# motoko_ice_dragon_x_dc.net
KiCad netlist of a schematic drawn in EAGLE
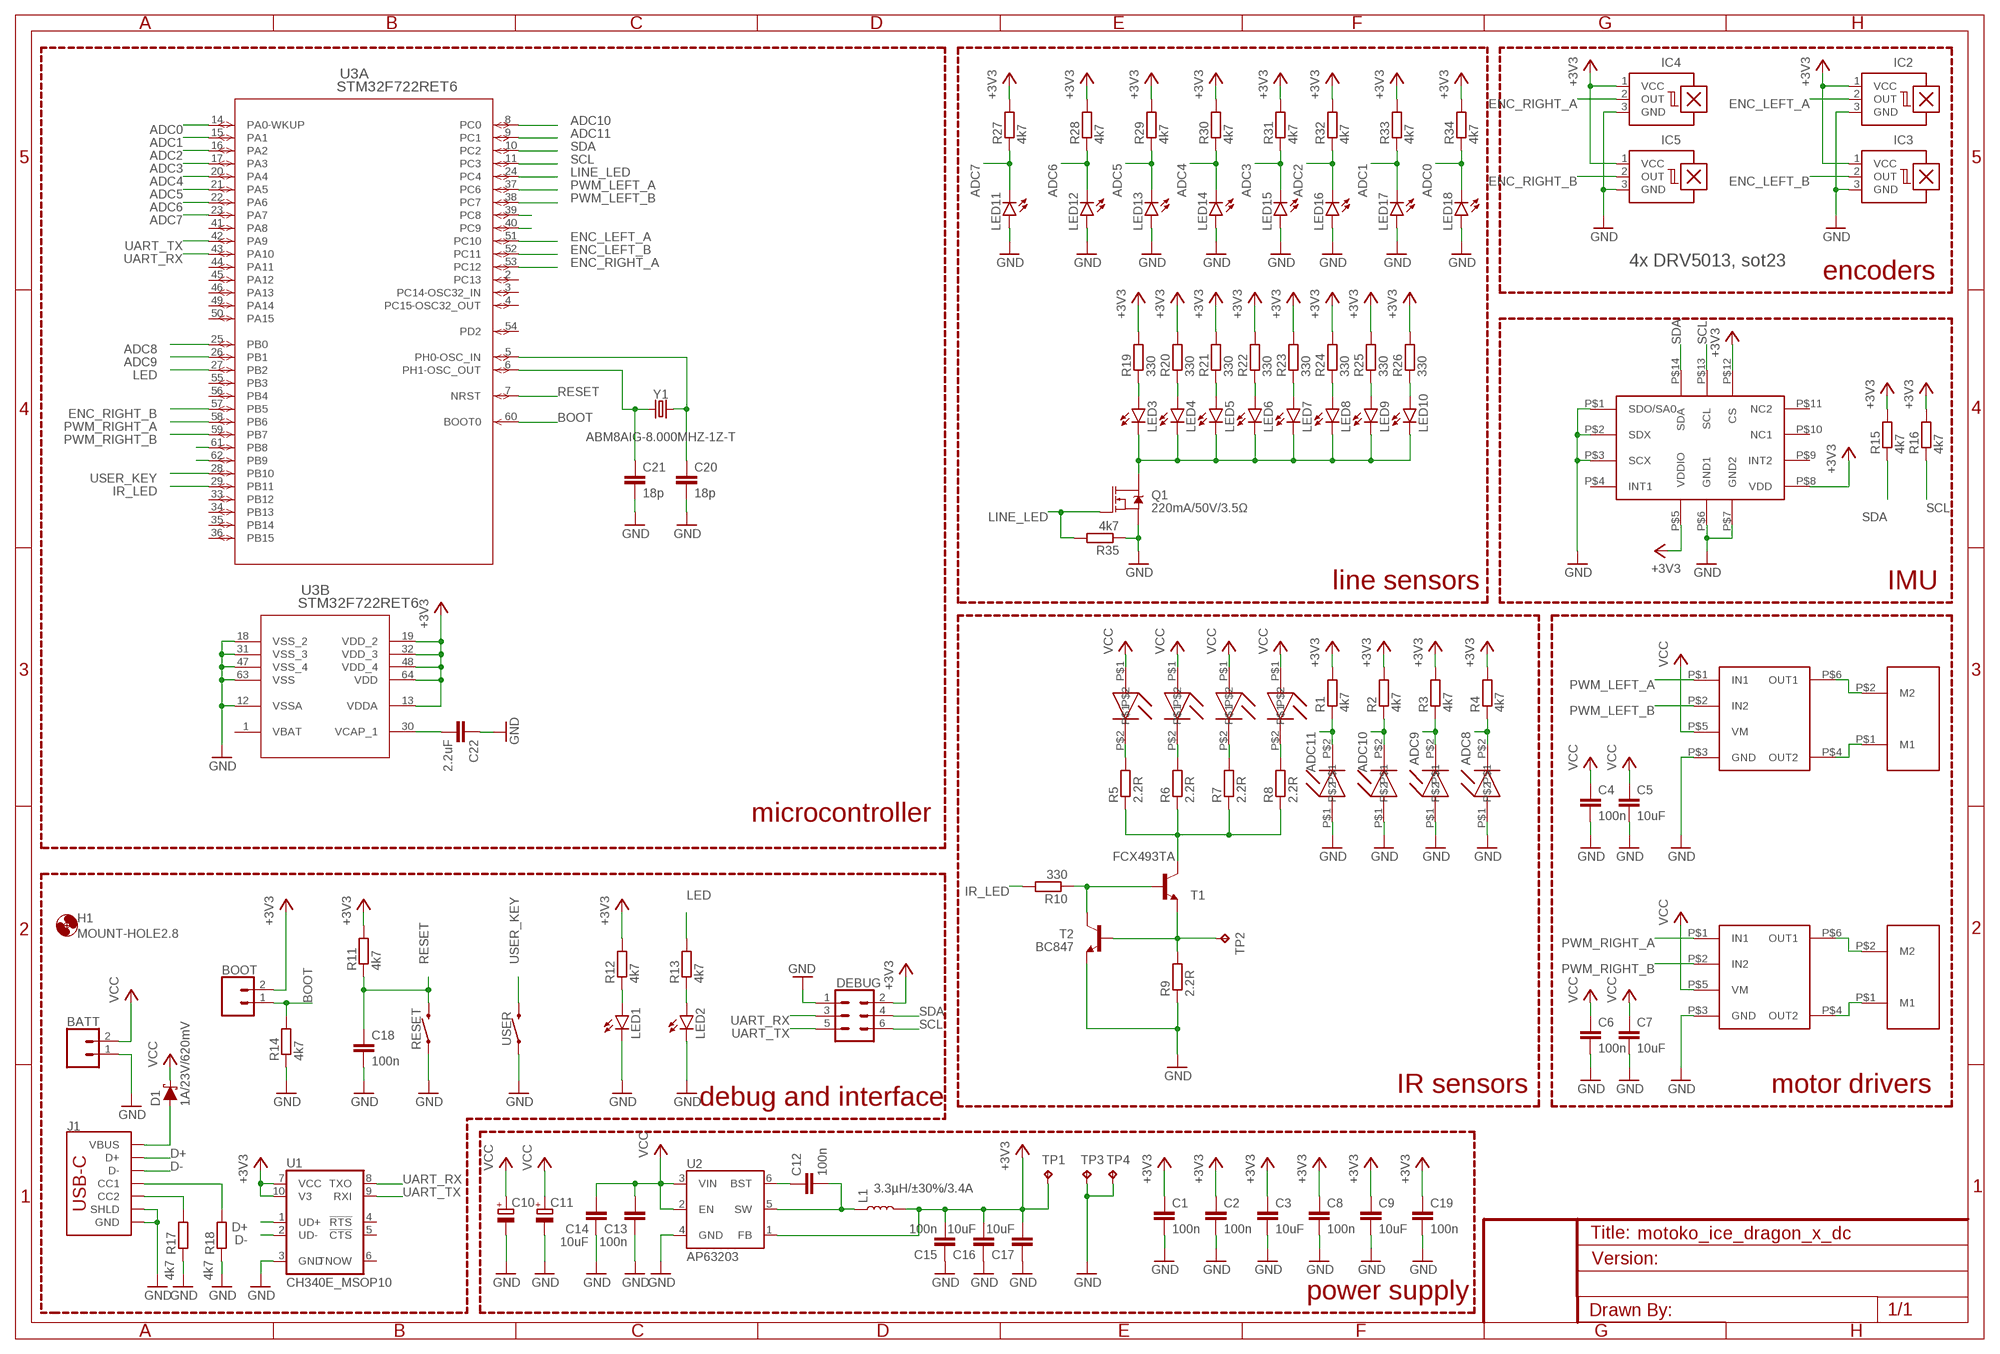
[diagram p0: schematic, sheet 1]

(export (version "E")
  (design (tool "Eeschema 10.0.6"))
  (components
    (comp (ref "BATT")
      (value "CONN_02LOCK_LONGPADS")
      (footprint "eagle-import:1X02_LOCK_LONGPADS")
      (libsource (lib "eagle-import") (part "CONN_02LOCK_LONGPADS"))
    )
    (comp (ref "BOOT")
      (value "CONN_02LOCK_LONGPADS")
      (footprint "eagle-import:1X02_LOCK_LONGPADS")
      (libsource (lib "eagle-import") (part "CONN_02LOCK_LONGPADS"))
    )
    (comp (ref "C1")
      (value "100n")
      (footprint "eagle-import:C0805")
      (libsource (lib "eagle-import") (part "C-EUC0805"))
    )
    (comp (ref "C2")
      (value "100n")
      (footprint "eagle-import:C0805")
      (libsource (lib "eagle-import") (part "C-EUC0805"))
    )
    (comp (ref "C3")
      (value "10uF")
      (footprint "eagle-import:C0805")
      (libsource (lib "eagle-import") (part "C-EUC0805"))
    )
    (comp (ref "C4")
      (value "100n")
      (footprint "eagle-import:C0805")
      (libsource (lib "eagle-import") (part "C-EUC0805"))
    )
    (comp (ref "C5")
      (value "10uF")
      (footprint "eagle-import:C0805")
      (libsource (lib "eagle-import") (part "C-EUC0805"))
    )
    (comp (ref "C6")
      (value "100n")
      (footprint "eagle-import:C0805")
      (libsource (lib "eagle-import") (part "C-EUC0805"))
    )
    (comp (ref "C7")
      (value "10uF")
      (footprint "eagle-import:C0805")
      (libsource (lib "eagle-import") (part "C-EUC0805"))
    )
    (comp (ref "C8")
      (value "100n")
      (footprint "eagle-import:C0805")
      (libsource (lib "eagle-import") (part "C-EUC0805"))
    )
    (comp (ref "C9")
      (value "10uF")
      (footprint "eagle-import:C0805")
      (libsource (lib "eagle-import") (part "C-EUC0805"))
    )
    (comp (ref "C10")
      (value "CPOL-EU140CLH-0810")
      (footprint "eagle-import:140CLH-0810")
      (libsource (lib "eagle-import") (part "CPOL-EU140CLH-0810"))
    )
    (comp (ref "C11")
      (value "CPOL-EU140CLH-0810")
      (footprint "eagle-import:140CLH-0810")
      (libsource (lib "eagle-import") (part "CPOL-EU140CLH-0810"))
    )
    (comp (ref "C12")
      (value "100n")
      (footprint "eagle-import:C0805")
      (libsource (lib "eagle-import") (part "C-EUC0805"))
    )
    (comp (ref "C13")
      (value "100n")
      (footprint "eagle-import:C0805")
      (libsource (lib "eagle-import") (part "C-EUC0805"))
    )
    (comp (ref "C14")
      (value "10uF")
      (footprint "eagle-import:C0805")
      (libsource (lib "eagle-import") (part "C-EUC0805"))
    )
    (comp (ref "C15")
      (value "100n")
      (footprint "eagle-import:C0805")
      (libsource (lib "eagle-import") (part "C-EUC0805"))
    )
    (comp (ref "C16")
      (value "10uF")
      (footprint "eagle-import:C0805")
      (libsource (lib "eagle-import") (part "C-EUC0805"))
    )
    (comp (ref "C17")
      (value "10uF")
      (footprint "eagle-import:C0805")
      (libsource (lib "eagle-import") (part "C-EUC0805"))
    )
    (comp (ref "C18")
      (value "100n")
      (footprint "eagle-import:C0805")
      (libsource (lib "eagle-import") (part "C-EUC0805"))
    )
    (comp (ref "C19")
      (value "100n")
      (footprint "eagle-import:C0805")
      (libsource (lib "eagle-import") (part "C-EUC0805"))
    )
    (comp (ref "C20")
      (value "18p")
      (footprint "eagle-import:C0805")
      (libsource (lib "eagle-import") (part "C-EUC0805"))
    )
    (comp (ref "C21")
      (value "18p")
      (footprint "eagle-import:C0805")
      (libsource (lib "eagle-import") (part "C-EUC0805"))
    )
    (comp (ref "C22")
      (value "2.2uF")
      (footprint "eagle-import:C0805")
      (libsource (lib "eagle-import") (part "C-EUC0805"))
    )
    (comp (ref "D1")
      (value "1A/23V/620mV")
      (footprint "eagle-import:SOD-323")
      (libsource (lib "eagle-import") (part "DIODE-SCHOTTKY-BAT20J"))
    )
    (comp (ref "DEBUG")
      (value "FEMALE 2x3")
      (footprint "eagle-import:2X3")
      (libsource (lib "eagle-import") (part "CONN_03X2FEMALE"))
    )
    (comp (ref "H1")
      (value "MOUNT-HOLE2.8")
      (footprint "eagle-import:2,8")
      (libsource (lib "eagle-import") (part "MOUNT-HOLE2.8"))
    )
    (comp (ref "IC2")
      (value "A1202LH")
      (footprint "eagle-import:SOT23-W")
      (libsource (lib "eagle-import") (part "A12?LH02"))
    )
    (comp (ref "IC3")
      (value "A1202LH")
      (footprint "eagle-import:SOT23-W")
      (libsource (lib "eagle-import") (part "A12?LH02"))
    )
    (comp (ref "IC4")
      (value "A1202LH")
      (footprint "eagle-import:SOT23-W")
      (libsource (lib "eagle-import") (part "A12?LH02"))
    )
    (comp (ref "IC5")
      (value "A1202LH")
      (footprint "eagle-import:SOT23-W")
      (libsource (lib "eagle-import") (part "A12?LH02"))
    )
    (comp (ref "J1")
      (value "640-USB4105-GF-A-120, man. GCT")
      (footprint "eagle-import:USB-C-16P-2LAYER-PADS")
      (libsource (lib "eagle-import") (part "USB_C_2-LAYER_PADS"))
    )
    (comp (ref "L1")
      (value "3.3µH/±30%/3.4A")
      (footprint "eagle-import:CR54")
      (libsource (lib "eagle-import") (part "INDUCTOR-CR54-3.3UH"))
    )
    (comp (ref "LED1")
      (value "LEDCHIPLED_1206")
      (footprint "eagle-import:CHIPLED_1206")
      (libsource (lib "eagle-import") (part "LEDCHIPLED_1206"))
    )
    (comp (ref "LED2")
      (value "LEDCHIPLED_1206")
      (footprint "eagle-import:CHIPLED_1206")
      (libsource (lib "eagle-import") (part "LEDCHIPLED_1206"))
    )
    (comp (ref "LED3")
      (value "LEDCHIPLED_1206")
      (footprint "eagle-import:CHIPLED_1206")
      (libsource (lib "eagle-import") (part "LEDCHIPLED_1206"))
    )
    (comp (ref "LED4")
      (value "LEDCHIPLED_1206")
      (footprint "eagle-import:CHIPLED_1206")
      (libsource (lib "eagle-import") (part "LEDCHIPLED_1206"))
    )
    (comp (ref "LED5")
      (value "LEDCHIPLED_1206")
      (footprint "eagle-import:CHIPLED_1206")
      (libsource (lib "eagle-import") (part "LEDCHIPLED_1206"))
    )
    (comp (ref "LED6")
      (value "LEDCHIPLED_1206")
      (footprint "eagle-import:CHIPLED_1206")
      (libsource (lib "eagle-import") (part "LEDCHIPLED_1206"))
    )
    (comp (ref "LED7")
      (value "LEDCHIPLED_1206")
      (footprint "eagle-import:CHIPLED_1206")
      (libsource (lib "eagle-import") (part "LEDCHIPLED_1206"))
    )
    (comp (ref "LED8")
      (value "LEDCHIPLED_1206")
      (footprint "eagle-import:CHIPLED_1206")
      (libsource (lib "eagle-import") (part "LEDCHIPLED_1206"))
    )
    (comp (ref "LED9")
      (value "LEDCHIPLED_1206")
      (footprint "eagle-import:CHIPLED_1206")
      (libsource (lib "eagle-import") (part "LEDCHIPLED_1206"))
    )
    (comp (ref "LED10")
      (value "LEDCHIPLED_1206")
      (footprint "eagle-import:CHIPLED_1206")
      (libsource (lib "eagle-import") (part "LEDCHIPLED_1206"))
    )
    (comp (ref "LED11")
      (value "LEDCHIPLED_1206")
      (footprint "eagle-import:CHIPLED_1206")
      (libsource (lib "eagle-import") (part "LEDCHIPLED_1206"))
    )
    (comp (ref "LED12")
      (value "LEDCHIPLED_1206")
      (footprint "eagle-import:CHIPLED_1206")
      (libsource (lib "eagle-import") (part "LEDCHIPLED_1206"))
    )
    (comp (ref "LED13")
      (value "LEDCHIPLED_1206")
      (footprint "eagle-import:CHIPLED_1206")
      (libsource (lib "eagle-import") (part "LEDCHIPLED_1206"))
    )
    (comp (ref "LED14")
      (value "LEDCHIPLED_1206")
      (footprint "eagle-import:CHIPLED_1206")
      (libsource (lib "eagle-import") (part "LEDCHIPLED_1206"))
    )
    (comp (ref "LED15")
      (value "LEDCHIPLED_1206")
      (footprint "eagle-import:CHIPLED_1206")
      (libsource (lib "eagle-import") (part "LEDCHIPLED_1206"))
    )
    (comp (ref "LED16")
      (value "LEDCHIPLED_1206")
      (footprint "eagle-import:CHIPLED_1206")
      (libsource (lib "eagle-import") (part "LEDCHIPLED_1206"))
    )
    (comp (ref "LED17")
      (value "LEDCHIPLED_1206")
      (footprint "eagle-import:CHIPLED_1206")
      (libsource (lib "eagle-import") (part "LEDCHIPLED_1206"))
    )
    (comp (ref "LED18")
      (value "LEDCHIPLED_1206")
      (footprint "eagle-import:CHIPLED_1206")
      (libsource (lib "eagle-import") (part "LEDCHIPLED_1206"))
    )
    (comp (ref "Q1")
      (value "220mA/50V/3.5Ω")
      (footprint "eagle-import:SOT23-3")
      (libsource (lib "eagle-import") (part "MOSFET-NCH-BSS138"))
    )
    (comp (ref "R1")
      (value "4k7")
      (footprint "eagle-import:M0805")
      (libsource (lib "eagle-import") (part "R-EU_M0805"))
    )
    (comp (ref "R2")
      (value "4k7")
      (footprint "eagle-import:M0805")
      (libsource (lib "eagle-import") (part "R-EU_M0805"))
    )
    (comp (ref "R3")
      (value "4k7")
      (footprint "eagle-import:M0805")
      (libsource (lib "eagle-import") (part "R-EU_M0805"))
    )
    (comp (ref "R4")
      (value "4k7")
      (footprint "eagle-import:M0805")
      (libsource (lib "eagle-import") (part "R-EU_M0805"))
    )
    (comp (ref "R5")
      (value "2.2R")
      (footprint "eagle-import:M0805")
      (libsource (lib "eagle-import") (part "R-EU_M0805"))
    )
    (comp (ref "R6")
      (value "2.2R")
      (footprint "eagle-import:M0805")
      (libsource (lib "eagle-import") (part "R-EU_M0805"))
    )
    (comp (ref "R7")
      (value "2.2R")
      (footprint "eagle-import:M0805")
      (libsource (lib "eagle-import") (part "R-EU_M0805"))
    )
    (comp (ref "R8")
      (value "2.2R")
      (footprint "eagle-import:M0805")
      (libsource (lib "eagle-import") (part "R-EU_M0805"))
    )
    (comp (ref "R9")
      (value "2.2R")
      (footprint "eagle-import:M0805")
      (libsource (lib "eagle-import") (part "R-EU_M0805"))
    )
    (comp (ref "R10")
      (value "330")
      (footprint "eagle-import:M0805")
      (libsource (lib "eagle-import") (part "R-EU_M0805"))
    )
    (comp (ref "R11")
      (value "4k7")
      (footprint "eagle-import:M0805")
      (libsource (lib "eagle-import") (part "R-EU_M0805"))
    )
    (comp (ref "R12")
      (value "4k7")
      (footprint "eagle-import:M0805")
      (libsource (lib "eagle-import") (part "R-EU_M0805"))
    )
    (comp (ref "R13")
      (value "4k7")
      (footprint "eagle-import:M0805")
      (libsource (lib "eagle-import") (part "R-EU_M0805"))
    )
    (comp (ref "R14")
      (value "4k7")
      (footprint "eagle-import:M0805")
      (libsource (lib "eagle-import") (part "R-EU_M0805"))
    )
    (comp (ref "R15")
      (value "4k7")
      (footprint "eagle-import:M0805")
      (libsource (lib "eagle-import") (part "R-EU_M0805"))
    )
    (comp (ref "R16")
      (value "4k7")
      (footprint "eagle-import:M0805")
      (libsource (lib "eagle-import") (part "R-EU_M0805"))
    )
    (comp (ref "R17")
      (value "4k7")
      (footprint "eagle-import:M0805")
      (libsource (lib "eagle-import") (part "R-EU_M0805"))
    )
    (comp (ref "R18")
      (value "4k7")
      (footprint "eagle-import:M0805")
      (libsource (lib "eagle-import") (part "R-EU_M0805"))
    )
    (comp (ref "R19")
      (value "330")
      (footprint "eagle-import:M0805")
      (libsource (lib "eagle-import") (part "R-EU_M0805"))
    )
    (comp (ref "R20")
      (value "330")
      (footprint "eagle-import:M0805")
      (libsource (lib "eagle-import") (part "R-EU_M0805"))
    )
    (comp (ref "R21")
      (value "330")
      (footprint "eagle-import:M0805")
      (libsource (lib "eagle-import") (part "R-EU_M0805"))
    )
    (comp (ref "R22")
      (value "330")
      (footprint "eagle-import:M0805")
      (libsource (lib "eagle-import") (part "R-EU_M0805"))
    )
    (comp (ref "R23")
      (value "330")
      (footprint "eagle-import:M0805")
      (libsource (lib "eagle-import") (part "R-EU_M0805"))
    )
    (comp (ref "R24")
      (value "330")
      (footprint "eagle-import:M0805")
      (libsource (lib "eagle-import") (part "R-EU_M0805"))
    )
    (comp (ref "R25")
      (value "330")
      (footprint "eagle-import:M0805")
      (libsource (lib "eagle-import") (part "R-EU_M0805"))
    )
    (comp (ref "R26")
      (value "330")
      (footprint "eagle-import:M0805")
      (libsource (lib "eagle-import") (part "R-EU_M0805"))
    )
    (comp (ref "R27")
      (value "4k7")
      (footprint "eagle-import:M0805")
      (libsource (lib "eagle-import") (part "R-EU_M0805"))
    )
    (comp (ref "R28")
      (value "4k7")
      (footprint "eagle-import:M0805")
      (libsource (lib "eagle-import") (part "R-EU_M0805"))
    )
    (comp (ref "R29")
      (value "4k7")
      (footprint "eagle-import:M0805")
      (libsource (lib "eagle-import") (part "R-EU_M0805"))
    )
    (comp (ref "R30")
      (value "4k7")
      (footprint "eagle-import:M0805")
      (libsource (lib "eagle-import") (part "R-EU_M0805"))
    )
    (comp (ref "R31")
      (value "4k7")
      (footprint "eagle-import:M0805")
      (libsource (lib "eagle-import") (part "R-EU_M0805"))
    )
    (comp (ref "R32")
      (value "4k7")
      (footprint "eagle-import:M0805")
      (libsource (lib "eagle-import") (part "R-EU_M0805"))
    )
    (comp (ref "R33")
      (value "4k7")
      (footprint "eagle-import:M0805")
      (libsource (lib "eagle-import") (part "R-EU_M0805"))
    )
    (comp (ref "R34")
      (value "4k7")
      (footprint "eagle-import:M0805")
      (libsource (lib "eagle-import") (part "R-EU_M0805"))
    )
    (comp (ref "R35")
      (value "4k7")
      (footprint "eagle-import:M0805")
      (libsource (lib "eagle-import") (part "R-EU_M0805"))
    )
    (comp (ref "RESET")
      (value "MOMENTARY-SWITCH-SPST-SMD-6.2MM-TALL")
      (footprint "eagle-import:TACTILE_SWITCH_SMD_6.2MM_TALL")
      (libsource (lib "eagle-import") (part "MOMENTARY-SWITCH-SPST-SMD-6.2MM-TALL"))
    )
    (comp (ref "T1")
      (value "FCX493TA")
      (footprint "eagle-import:SOT89-BCE")
      (libsource (lib "eagle-import") (part "-NPN-SOT89-BCE"))
    )
    (comp (ref "T2")
      (value "BC847")
      (footprint "eagle-import:SOT23")
      (libsource (lib "eagle-import") (part "BC847"))
    )
    (comp (ref "TP1")
      (value "TPB1,27")
      (footprint "eagle-import:B1,27")
      (libsource (lib "eagle-import") (part "TPB1,27"))
    )
    (comp (ref "TP2")
      (value "TPB1,27")
      (footprint "eagle-import:B1,27")
      (libsource (lib "eagle-import") (part "TPB1,27"))
    )
    (comp (ref "TP3")
      (value "TPB1,27")
      (footprint "eagle-import:B1,27")
      (libsource (lib "eagle-import") (part "TPB1,27"))
    )
    (comp (ref "TP4")
      (value "TPB1,27")
      (footprint "eagle-import:B1,27")
      (libsource (lib "eagle-import") (part "TPB1,27"))
    )
    (comp (ref "U$1")
      (value "DRV8212")
      (footprint "eagle-import:SOT_0.6MM")
      (libsource (lib "eagle-import") (part "DRV8212"))
    )
    (comp (ref "U$3")
      (value "DRV8212")
      (footprint "eagle-import:SOT_0.6MM")
      (libsource (lib "eagle-import") (part "DRV8212"))
    )
    (comp (ref "U$4")
      (value "POLOLU_MICRO_METAL_GEAR_MOTOR")
      (footprint "eagle-import:POLOLU_MICRO_METAL_GEAR_MOTOR")
      (libsource (lib "eagle-import") (part "POLOLU_MICRO_METAL_GEAR_MOTOR"))
    )
    (comp (ref "U$5")
      (value "POLOLU_MICRO_METAL_GEAR_MOTOR")
      (footprint "eagle-import:POLOLU_MICRO_METAL_GEAR_MOTOR")
      (libsource (lib "eagle-import") (part "POLOLU_MICRO_METAL_GEAR_MOTOR"))
    )
    (comp (ref "U$6")
      (value "LSM6DSM")
      (footprint "eagle-import:LGA14L")
      (libsource (lib "eagle-import") (part "LSM6DSM"))
    )
    (comp (ref "U$7")
      (value "LED_5MM_AXIAL")
      (footprint "eagle-import:LED_5MM_AXIAL")
      (libsource (lib "eagle-import") (part "LED_5MM_AXIAL"))
    )
    (comp (ref "U$8")
      (value "LED_5MM_AXIAL")
      (footprint "eagle-import:LED_5MM_AXIAL")
      (libsource (lib "eagle-import") (part "LED_5MM_AXIAL"))
    )
    (comp (ref "U$9")
      (value "LED_5MM_AXIAL")
      (footprint "eagle-import:LED_5MM_AXIAL")
      (libsource (lib "eagle-import") (part "LED_5MM_AXIAL"))
    )
    (comp (ref "U$10")
      (value "LED_5MM_AXIAL")
      (footprint "eagle-import:LED_5MM_AXIAL")
      (libsource (lib "eagle-import") (part "LED_5MM_AXIAL"))
    )
    (comp (ref "U$11")
      (value "LED_5MM_AXIAL")
      (footprint "eagle-import:LED_5MM_AXIAL")
      (libsource (lib "eagle-import") (part "LED_5MM_AXIAL"))
    )
    (comp (ref "U$12")
      (value "LED_5MM_AXIAL")
      (footprint "eagle-import:LED_5MM_AXIAL")
      (fields (field (name "SPICEPREFIX") "B"))
      (libsource (lib "eagle-import") (part "LED_5MM_AXIAL"))
    )
    (comp (ref "U$13")
      (value "LED_5MM_AXIAL")
      (footprint "eagle-import:LED_5MM_AXIAL")
      (libsource (lib "eagle-import") (part "LED_5MM_AXIAL"))
    )
    (comp (ref "U$14")
      (value "LED_5MM_AXIAL")
      (footprint "eagle-import:LED_5MM_AXIAL")
      (libsource (lib "eagle-import") (part "LED_5MM_AXIAL"))
    )
    (comp (ref "U1")
      (value "CH340E_MSOP10")
      (footprint "eagle-import:MSOP10")
      (libsource (lib "eagle-import") (part "CH340E_MSOP10"))
    )
    (comp (ref "U2")
      (value "AP63203")
      (footprint "eagle-import:SOT23-6")
      (libsource (lib "eagle-import") (part "AP63203"))
    )
    (comp (ref "U3")
      (value "STM32F722RET6")
      (footprint "eagle-import:LQFP64-10X10MM")
      (fields (field (name "COPYRIGHT") "Copyright (C) 2024 Ultra Librarian. All rights reserved."))
      (libsource (lib "eagle-import") (part "STM32F722RET6"))
    )
    (comp (ref "USER")
      (value "MOMENTARY-SWITCH-SPST-SMD-6.2MM-TALL")
      (footprint "eagle-import:TACTILE_SWITCH_SMD_6.2MM_TALL")
      (libsource (lib "eagle-import") (part "MOMENTARY-SWITCH-SPST-SMD-6.2MM-TALL"))
    )
    (comp (ref "Y1")
      (value "ABM8AIG-8.000MHZ-1Z-T")
      (footprint "eagle-import:CRYSTAL-SMD-3.2X2.5MM")
      (libsource (lib "eagle-import") (part "CRYSTALSMD-3.2X2.5"))
    )
  )
  (nets
    (net (code "1") (name "+3V3") (class "Default")
      (node (ref "BOOT") (pin "2") (pinfunction "2_2") (pintype "passive"))
      (node (ref "C1") (pin "1") (pinfunction "1_1") (pintype "passive"))
      (node (ref "C15") (pin "2") (pinfunction "2_2") (pintype "passive"))
      (node (ref "C16") (pin "2") (pinfunction "2_2") (pintype "passive"))
      (node (ref "C17") (pin "2") (pinfunction "2_2") (pintype "passive"))
      (node (ref "C19") (pin "1") (pinfunction "1_1") (pintype "passive"))
      (node (ref "C2") (pin "1") (pinfunction "1_1") (pintype "passive"))
      (node (ref "C3") (pin "1") (pinfunction "1_1") (pintype "passive"))
      (node (ref "C8") (pin "1") (pinfunction "1_1") (pintype "passive"))
      (node (ref "C9") (pin "1") (pinfunction "1_1") (pintype "passive"))
      (node (ref "DEBUG") (pin "2") (pinfunction "2_2") (pintype "bidirectional"))
      (node (ref "IC2") (pin "1") (pinfunction "VCC_1") (pintype "power_in"))
      (node (ref "IC3") (pin "1") (pinfunction "VCC_1") (pintype "power_in"))
      (node (ref "IC4") (pin "1") (pinfunction "VCC_1") (pintype "power_in"))
      (node (ref "IC5") (pin "1") (pinfunction "VCC_1") (pintype "power_in"))
      (node (ref "L1") (pin "P$2") (pinfunction "2_P$2") (pintype "passive"))
      (node (ref "R1") (pin "2") (pinfunction "2_2") (pintype "passive"))
      (node (ref "R11") (pin "2") (pinfunction "2_2") (pintype "passive"))
      (node (ref "R12") (pin "2") (pinfunction "2_2") (pintype "passive"))
      (node (ref "R15") (pin "2") (pinfunction "2_2") (pintype "passive"))
      (node (ref "R16") (pin "2") (pinfunction "2_2") (pintype "passive"))
      (node (ref "R19") (pin "2") (pinfunction "2_2") (pintype "passive"))
      (node (ref "R2") (pin "2") (pinfunction "2_2") (pintype "passive"))
      (node (ref "R20") (pin "2") (pinfunction "2_2") (pintype "passive"))
      (node (ref "R21") (pin "2") (pinfunction "2_2") (pintype "passive"))
      (node (ref "R22") (pin "2") (pinfunction "2_2") (pintype "passive"))
      (node (ref "R23") (pin "2") (pinfunction "2_2") (pintype "passive"))
      (node (ref "R24") (pin "2") (pinfunction "2_2") (pintype "passive"))
      (node (ref "R25") (pin "2") (pinfunction "2_2") (pintype "passive"))
      (node (ref "R26") (pin "2") (pinfunction "2_2") (pintype "passive"))
      (node (ref "R27") (pin "2") (pinfunction "2_2") (pintype "passive"))
      (node (ref "R28") (pin "2") (pinfunction "2_2") (pintype "passive"))
      (node (ref "R29") (pin "2") (pinfunction "2_2") (pintype "passive"))
      (node (ref "R3") (pin "2") (pinfunction "2_2") (pintype "passive"))
      (node (ref "R30") (pin "2") (pinfunction "2_2") (pintype "passive"))
      (node (ref "R31") (pin "2") (pinfunction "2_2") (pintype "passive"))
      (node (ref "R32") (pin "2") (pinfunction "2_2") (pintype "passive"))
      (node (ref "R33") (pin "2") (pinfunction "2_2") (pintype "passive"))
      (node (ref "R34") (pin "2") (pinfunction "2_2") (pintype "passive"))
      (node (ref "R4") (pin "2") (pinfunction "2_2") (pintype "passive"))
      (node (ref "TP1") (pin "TP") (pinfunction "TP_TP") (pintype "input"))
      (node (ref "U$6") (pin "P$12") (pinfunction "CS_P$12") (pintype "bidirectional"))
      (node (ref "U$6") (pin "P$5") (pinfunction "VDDIO_P$5") (pintype "bidirectional"))
      (node (ref "U$6") (pin "P$8") (pinfunction "VDD_P$8") (pintype "bidirectional"))
      (node (ref "U1") (pin "10") (pinfunction "V3_10") (pintype "bidirectional"))
      (node (ref "U1") (pin "7") (pinfunction "VCC_7") (pintype "bidirectional"))
      (node (ref "U2") (pin "1") (pinfunction "FB_1") (pintype "bidirectional"))
      (node (ref "U3") (pin "13") (pinfunction "VDDA_13") (pintype "power_in"))
      (node (ref "U3") (pin "19") (pinfunction "VDD_2_19") (pintype "power_in"))
      (node (ref "U3") (pin "32") (pinfunction "VDD_3_32") (pintype "power_in"))
      (node (ref "U3") (pin "48") (pinfunction "VDD_4_48") (pintype "power_in"))
      (node (ref "U3") (pin "64") (pinfunction "VDD_64") (pintype "power_in"))
    )
    (net (code "2") (name "/ADC0") (class "Default")
      (node (ref "LED18") (pin "C") (pinfunction "C_C") (pintype "passive"))
      (node (ref "R34") (pin "1") (pinfunction "1_1") (pintype "passive"))
      (node (ref "U3") (pin "14") (pinfunction "PA0-WKUP_14") (pintype "bidirectional"))
    )
    (net (code "3") (name "/ADC1") (class "Default")
      (node (ref "LED17") (pin "C") (pinfunction "C_C") (pintype "passive"))
      (node (ref "R33") (pin "1") (pinfunction "1_1") (pintype "passive"))
      (node (ref "U3") (pin "15") (pinfunction "PA1_15") (pintype "bidirectional"))
    )
    (net (code "4") (name "/ADC2") (class "Default")
      (node (ref "LED16") (pin "C") (pinfunction "C_C") (pintype "passive"))
      (node (ref "R32") (pin "1") (pinfunction "1_1") (pintype "passive"))
      (node (ref "U3") (pin "16") (pinfunction "PA2_16") (pintype "bidirectional"))
    )
    (net (code "5") (name "/ADC3") (class "Default")
      (node (ref "LED15") (pin "C") (pinfunction "C_C") (pintype "passive"))
      (node (ref "R31") (pin "1") (pinfunction "1_1") (pintype "passive"))
      (node (ref "U3") (pin "17") (pinfunction "PA3_17") (pintype "bidirectional"))
    )
    (net (code "6") (name "/ADC4") (class "Default")
      (node (ref "LED14") (pin "C") (pinfunction "C_C") (pintype "passive"))
      (node (ref "R30") (pin "1") (pinfunction "1_1") (pintype "passive"))
      (node (ref "U3") (pin "20") (pinfunction "PA4_20") (pintype "bidirectional"))
    )
    (net (code "7") (name "/ADC5") (class "Default")
      (node (ref "LED13") (pin "C") (pinfunction "C_C") (pintype "passive"))
      (node (ref "R29") (pin "1") (pinfunction "1_1") (pintype "passive"))
      (node (ref "U3") (pin "21") (pinfunction "PA5_21") (pintype "bidirectional"))
    )
    (net (code "8") (name "/ADC6") (class "Default")
      (node (ref "LED12") (pin "C") (pinfunction "C_C") (pintype "passive"))
      (node (ref "R28") (pin "1") (pinfunction "1_1") (pintype "passive"))
      (node (ref "U3") (pin "22") (pinfunction "PA6_22") (pintype "bidirectional"))
    )
    (net (code "9") (name "/ADC7") (class "Default")
      (node (ref "LED11") (pin "C") (pinfunction "C_C") (pintype "passive"))
      (node (ref "R27") (pin "1") (pinfunction "1_1") (pintype "passive"))
      (node (ref "U3") (pin "23") (pinfunction "PA7_23") (pintype "bidirectional"))
    )
    (net (code "10") (name "/ADC8") (class "Default")
      (node (ref "R4") (pin "1") (pinfunction "1_1") (pintype "passive"))
      (node (ref "U$7") (pin "P$2") (pinfunction "P$2_P$2") (pintype "bidirectional"))
      (node (ref "U3") (pin "25") (pinfunction "PB0_25") (pintype "bidirectional"))
    )
    (net (code "11") (name "/ADC9") (class "Default")
      (node (ref "R3") (pin "1") (pinfunction "1_1") (pintype "passive"))
      (node (ref "U$11") (pin "P$2") (pinfunction "P$2_P$2") (pintype "bidirectional"))
      (node (ref "U3") (pin "26") (pinfunction "PB1_26") (pintype "bidirectional"))
    )
    (net (code "12") (name "/ADC10") (class "Default")
      (node (ref "R2") (pin "1") (pinfunction "1_1") (pintype "passive"))
      (node (ref "U$14") (pin "P$2") (pinfunction "P$2_P$2") (pintype "bidirectional"))
      (node (ref "U3") (pin "8") (pinfunction "PC0_8") (pintype "bidirectional"))
    )
    (net (code "13") (name "/ADC11") (class "Default")
      (node (ref "R1") (pin "1") (pinfunction "1_1") (pintype "passive"))
      (node (ref "U$9") (pin "P$2") (pinfunction "P$2_P$2") (pintype "bidirectional"))
      (node (ref "U3") (pin "9") (pinfunction "PC1_9") (pintype "bidirectional"))
    )
    (net (code "14") (name "/BOOT") (class "Default")
      (node (ref "BOOT") (pin "1") (pinfunction "1_1") (pintype "passive"))
      (node (ref "R14") (pin "2") (pinfunction "2_2") (pintype "passive"))
      (node (ref "U3") (pin "60") (pinfunction "BOOT0_60") (pintype "input"))
    )
    (net (code "15") (name "/D+") (class "Default")
      (node (ref "J1") (pin "A6") (pinfunction "D+_A6") (pintype "bidirectional"))
      (node (ref "J1") (pin "B6") (pinfunction "D+_B6") (pintype "bidirectional"))
      (node (ref "U1") (pin "1") (pinfunction "UD+_1") (pintype "bidirectional"))
    )
    (net (code "16") (name "/D-") (class "Default")
      (node (ref "J1") (pin "A7") (pinfunction "D-_A7") (pintype "bidirectional"))
      (node (ref "J1") (pin "B7") (pinfunction "D-_B7") (pintype "bidirectional"))
      (node (ref "U1") (pin "2") (pinfunction "UD-_2") (pintype "bidirectional"))
    )
    (net (code "17") (name "/ENC_LEFT_A") (class "Default")
      (node (ref "IC2") (pin "2") (pinfunction "OUT_2") (pintype "output"))
      (node (ref "U3") (pin "51") (pinfunction "PC10_51") (pintype "bidirectional"))
    )
    (net (code "18") (name "/ENC_LEFT_B") (class "Default")
      (node (ref "IC3") (pin "2") (pinfunction "OUT_2") (pintype "output"))
      (node (ref "U3") (pin "52") (pinfunction "PC11_52") (pintype "bidirectional"))
    )
    (net (code "19") (name "/ENC_RIGHT_A") (class "Default")
      (node (ref "IC4") (pin "2") (pinfunction "OUT_2") (pintype "output"))
      (node (ref "U3") (pin "53") (pinfunction "PC12_53") (pintype "bidirectional"))
    )
    (net (code "20") (name "/ENC_RIGHT_B") (class "Default")
      (node (ref "IC5") (pin "2") (pinfunction "OUT_2") (pintype "output"))
      (node (ref "U3") (pin "57") (pinfunction "PB5_57") (pintype "bidirectional"))
    )
    (net (code "21") (name "/IR_LED") (class "Default")
      (node (ref "R10") (pin "2") (pinfunction "2_2") (pintype "passive"))
      (node (ref "U3") (pin "29") (pinfunction "PB11_29") (pintype "bidirectional"))
    )
    (net (code "22") (name "/LED") (class "Default")
      (node (ref "R13") (pin "2") (pinfunction "2_2") (pintype "passive"))
      (node (ref "U3") (pin "27") (pinfunction "PB2_27") (pintype "bidirectional"))
    )
    (net (code "23") (name "/LINE_LED") (class "Default")
      (node (ref "Q1") (pin "1") (pinfunction "G_1") (pintype "bidirectional"))
      (node (ref "R35") (pin "2") (pinfunction "2_2") (pintype "passive"))
      (node (ref "U3") (pin "24") (pinfunction "PC4_24") (pintype "bidirectional"))
    )
    (net (code "24") (name "/PWM_LEFT_A") (class "Default")
      (node (ref "U$1") (pin "P$1") (pinfunction "IN1_P$1") (pintype "bidirectional"))
      (node (ref "U3") (pin "37") (pinfunction "PC6_37") (pintype "bidirectional"))
    )
    (net (code "25") (name "/PWM_LEFT_B") (class "Default")
      (node (ref "U$1") (pin "P$2") (pinfunction "IN2_P$2") (pintype "bidirectional"))
      (node (ref "U3") (pin "38") (pinfunction "PC7_38") (pintype "bidirectional"))
    )
    (net (code "26") (name "/PWM_RIGHT_A") (class "Default")
      (node (ref "U$3") (pin "P$1") (pinfunction "IN1_P$1") (pintype "bidirectional"))
      (node (ref "U3") (pin "58") (pinfunction "PB6_58") (pintype "bidirectional"))
    )
    (net (code "27") (name "/PWM_RIGHT_B") (class "Default")
      (node (ref "U$3") (pin "P$2") (pinfunction "IN2_P$2") (pintype "bidirectional"))
      (node (ref "U3") (pin "59") (pinfunction "PB7_59") (pintype "bidirectional"))
    )
    (net (code "28") (name "/RESET") (class "Default")
      (node (ref "C18") (pin "1") (pinfunction "1_1") (pintype "passive"))
      (node (ref "R11") (pin "1") (pinfunction "1_1") (pintype "passive"))
      (node (ref "RESET") (pin "B2") (pinfunction "2_B2") (pintype "passive"))
      (node (ref "U3") (pin "7") (pinfunction "NRST_7") (pintype "bidirectional"))
    )
    (net (code "29") (name "/SCL") (class "Default")
      (node (ref "DEBUG") (pin "6") (pinfunction "6_6") (pintype "bidirectional"))
      (node (ref "R16") (pin "1") (pinfunction "1_1") (pintype "passive"))
      (node (ref "U$6") (pin "P$13") (pinfunction "SCL_P$13") (pintype "bidirectional"))
      (node (ref "U3") (pin "11") (pinfunction "PC3_11") (pintype "bidirectional"))
    )
    (net (code "30") (name "/SDA") (class "Default")
      (node (ref "DEBUG") (pin "4") (pinfunction "4_4") (pintype "bidirectional"))
      (node (ref "R15") (pin "1") (pinfunction "1_1") (pintype "passive"))
      (node (ref "U$6") (pin "P$14") (pinfunction "SDA_P$14") (pintype "bidirectional"))
      (node (ref "U3") (pin "10") (pinfunction "PC2_10") (pintype "bidirectional"))
    )
    (net (code "31") (name "/UART_RX") (class "Default")
      (node (ref "DEBUG") (pin "3") (pinfunction "3_3") (pintype "bidirectional"))
      (node (ref "U1") (pin "8") (pinfunction "TXO_8") (pintype "bidirectional"))
      (node (ref "U3") (pin "43") (pinfunction "PA10_43") (pintype "bidirectional"))
    )
    (net (code "32") (name "/UART_TX") (class "Default")
      (node (ref "DEBUG") (pin "5") (pinfunction "5_5") (pintype "bidirectional"))
      (node (ref "U1") (pin "9") (pinfunction "RXI_9") (pintype "bidirectional"))
      (node (ref "U3") (pin "42") (pinfunction "PA9_42") (pintype "bidirectional"))
    )
    (net (code "33") (name "/USER_KEY") (class "Default")
      (node (ref "U3") (pin "28") (pinfunction "PB10_28") (pintype "bidirectional"))
      (node (ref "USER") (pin "B2") (pinfunction "2_B2") (pintype "passive"))
    )
    (net (code "34") (name "/VBAT") (class "Default")
      (node (ref "U3") (pin "1") (pinfunction "VBAT_1") (pintype "power_in"))
    )
    (net (code "35") (name "GND") (class "Default")
      (node (ref "BATT") (pin "1") (pinfunction "1_1") (pintype "passive"))
      (node (ref "C1") (pin "2") (pinfunction "2_2") (pintype "passive"))
      (node (ref "C10") (pin "-") (pinfunction "-_-") (pintype "passive"))
      (node (ref "C11") (pin "-") (pinfunction "-_-") (pintype "passive"))
      (node (ref "C13") (pin "1") (pinfunction "1_1") (pintype "passive"))
      (node (ref "C14") (pin "1") (pinfunction "1_1") (pintype "passive"))
      (node (ref "C15") (pin "1") (pinfunction "1_1") (pintype "passive"))
      (node (ref "C16") (pin "1") (pinfunction "1_1") (pintype "passive"))
      (node (ref "C17") (pin "1") (pinfunction "1_1") (pintype "passive"))
      (node (ref "C18") (pin "2") (pinfunction "2_2") (pintype "passive"))
      (node (ref "C19") (pin "2") (pinfunction "2_2") (pintype "passive"))
      (node (ref "C2") (pin "2") (pinfunction "2_2") (pintype "passive"))
      (node (ref "C20") (pin "2") (pinfunction "2_2") (pintype "passive"))
      (node (ref "C21") (pin "2") (pinfunction "2_2") (pintype "passive"))
      (node (ref "C22") (pin "1") (pinfunction "1_1") (pintype "passive"))
      (node (ref "C3") (pin "2") (pinfunction "2_2") (pintype "passive"))
      (node (ref "C4") (pin "2") (pinfunction "2_2") (pintype "passive"))
      (node (ref "C5") (pin "2") (pinfunction "2_2") (pintype "passive"))
      (node (ref "C6") (pin "2") (pinfunction "2_2") (pintype "passive"))
      (node (ref "C7") (pin "2") (pinfunction "2_2") (pintype "passive"))
      (node (ref "C8") (pin "2") (pinfunction "2_2") (pintype "passive"))
      (node (ref "C9") (pin "2") (pinfunction "2_2") (pintype "passive"))
      (node (ref "DEBUG") (pin "1") (pinfunction "1_1") (pintype "bidirectional"))
      (node (ref "IC2") (pin "3") (pinfunction "GND_3") (pintype "power_in"))
      (node (ref "IC3") (pin "3") (pinfunction "GND_3") (pintype "power_in"))
      (node (ref "IC4") (pin "3") (pinfunction "GND_3") (pintype "power_in"))
      (node (ref "IC5") (pin "3") (pinfunction "GND_3") (pintype "power_in"))
      (node (ref "J1") (pin "GND") (pinfunction "GND_GND") (pintype "bidirectional"))
      (node (ref "J1") (pin "GND2") (pinfunction "GND_GND2") (pintype "bidirectional"))
      (node (ref "J1") (pin "SHLD1") (pinfunction "SHLD_SHLD1") (pintype "bidirectional"))
      (node (ref "J1") (pin "SHLD2") (pinfunction "SHLD_SHLD2") (pintype "bidirectional"))
      (node (ref "J1") (pin "SHLD3") (pinfunction "SHLD_SHLD3") (pintype "bidirectional"))
      (node (ref "J1") (pin "SHLD4") (pinfunction "SHLD_SHLD4") (pintype "bidirectional"))
      (node (ref "LED1") (pin "C") (pinfunction "C_C") (pintype "passive"))
      (node (ref "LED11") (pin "A") (pinfunction "A_A") (pintype "passive"))
      (node (ref "LED12") (pin "A") (pinfunction "A_A") (pintype "passive"))
      (node (ref "LED13") (pin "A") (pinfunction "A_A") (pintype "passive"))
      (node (ref "LED14") (pin "A") (pinfunction "A_A") (pintype "passive"))
      (node (ref "LED15") (pin "A") (pinfunction "A_A") (pintype "passive"))
      (node (ref "LED16") (pin "A") (pinfunction "A_A") (pintype "passive"))
      (node (ref "LED17") (pin "A") (pinfunction "A_A") (pintype "passive"))
      (node (ref "LED18") (pin "A") (pinfunction "A_A") (pintype "passive"))
      (node (ref "LED2") (pin "C") (pinfunction "C_C") (pintype "passive"))
      (node (ref "Q1") (pin "2") (pinfunction "S_2") (pintype "bidirectional"))
      (node (ref "R14") (pin "1") (pinfunction "1_1") (pintype "passive"))
      (node (ref "R17") (pin "1") (pinfunction "1_1") (pintype "passive"))
      (node (ref "R18") (pin "1") (pinfunction "1_1") (pintype "passive"))
      (node (ref "R35") (pin "1") (pinfunction "1_1") (pintype "passive"))
      (node (ref "R9") (pin "1") (pinfunction "1_1") (pintype "passive"))
      (node (ref "RESET") (pin "A2") (pinfunction "1_A2") (pintype "passive"))
      (node (ref "T2") (pin "2") (pinfunction "E_2") (pintype "passive"))
      (node (ref "TP3") (pin "TP") (pinfunction "TP_TP") (pintype "input"))
      (node (ref "TP4") (pin "TP") (pinfunction "TP_TP") (pintype "input"))
      (node (ref "U$1") (pin "P$3") (pinfunction "GND_P$3") (pintype "bidirectional"))
      (node (ref "U$11") (pin "P$1") (pinfunction "P$1_P$1") (pintype "bidirectional"))
      (node (ref "U$14") (pin "P$1") (pinfunction "P$1_P$1") (pintype "bidirectional"))
      (node (ref "U$3") (pin "P$3") (pinfunction "GND_P$3") (pintype "bidirectional"))
      (node (ref "U$6") (pin "P$1") (pinfunction "SDO/SA0_P$1") (pintype "bidirectional"))
      (node (ref "U$6") (pin "P$2") (pinfunction "SDX_P$2") (pintype "bidirectional"))
      (node (ref "U$6") (pin "P$3") (pinfunction "SCX_P$3") (pintype "bidirectional"))
      (node (ref "U$6") (pin "P$6") (pinfunction "GND1_P$6") (pintype "bidirectional"))
      (node (ref "U$6") (pin "P$7") (pinfunction "GND2_P$7") (pintype "bidirectional"))
      (node (ref "U$7") (pin "P$1") (pinfunction "P$1_P$1") (pintype "bidirectional"))
      (node (ref "U$9") (pin "P$1") (pinfunction "P$1_P$1") (pintype "bidirectional"))
      (node (ref "U1") (pin "3") (pinfunction "GND_3") (pintype "bidirectional"))
      (node (ref "U2") (pin "4") (pinfunction "GND_4") (pintype "bidirectional"))
      (node (ref "U3") (pin "12") (pinfunction "VSSA_12") (pintype "power_in"))
      (node (ref "U3") (pin "18") (pinfunction "VSS_2_18") (pintype "power_in"))
      (node (ref "U3") (pin "31") (pinfunction "VSS_3_31") (pintype "power_in"))
      (node (ref "U3") (pin "47") (pinfunction "VSS_4_47") (pintype "power_in"))
      (node (ref "U3") (pin "63") (pinfunction "VSS_63") (pintype "power_in"))
      (node (ref "USER") (pin "A2") (pinfunction "1_A2") (pintype "passive"))
    )
    (net (code "36") (name "Net-(D1-PadA)") (class "Default")
      (node (ref "D1") (pin "A") (pinfunction "A_A") (pintype "passive"))
      (node (ref "J1") (pin "VBUS1") (pinfunction "VBUS_VBUS1") (pintype "bidirectional"))
      (node (ref "J1") (pin "VBUS2") (pinfunction "VBUS_VBUS2") (pintype "bidirectional"))
    )
    (net (code "37") (name "Net-(J1-CC1)") (class "Default")
      (node (ref "J1") (pin "A5") (pinfunction "CC1_A5") (pintype "bidirectional"))
      (node (ref "R18") (pin "2") (pinfunction "2_2") (pintype "passive"))
    )
    (net (code "38") (name "Net-(J1-CC2)") (class "Default")
      (node (ref "J1") (pin "B5") (pinfunction "CC2_B5") (pintype "bidirectional"))
      (node (ref "R17") (pin "2") (pinfunction "2_2") (pintype "passive"))
    )
    (net (code "39") (name "Net-(L1-1)") (class "Default")
      (node (ref "C12") (pin "2") (pinfunction "2_2") (pintype "passive"))
      (node (ref "L1") (pin "P$1") (pinfunction "1_P$1") (pintype "passive"))
      (node (ref "U2") (pin "5") (pinfunction "SW_5") (pintype "bidirectional"))
    )
    (net (code "40") (name "Net-(LED1-PadA)") (class "Default")
      (node (ref "LED1") (pin "A") (pinfunction "A_A") (pintype "passive"))
      (node (ref "R12") (pin "1") (pinfunction "1_1") (pintype "passive"))
    )
    (net (code "41") (name "Net-(LED2-PadA)") (class "Default")
      (node (ref "LED2") (pin "A") (pinfunction "A_A") (pintype "passive"))
      (node (ref "R13") (pin "1") (pinfunction "1_1") (pintype "passive"))
    )
    (net (code "42") (name "Net-(LED3-PadA)") (class "Default")
      (node (ref "LED3") (pin "A") (pinfunction "A_A") (pintype "passive"))
      (node (ref "R19") (pin "1") (pinfunction "1_1") (pintype "passive"))
    )
    (net (code "43") (name "Net-(LED4-PadA)") (class "Default")
      (node (ref "LED4") (pin "A") (pinfunction "A_A") (pintype "passive"))
      (node (ref "R20") (pin "1") (pinfunction "1_1") (pintype "passive"))
    )
    (net (code "44") (name "Net-(LED5-PadA)") (class "Default")
      (node (ref "LED5") (pin "A") (pinfunction "A_A") (pintype "passive"))
      (node (ref "R21") (pin "1") (pinfunction "1_1") (pintype "passive"))
    )
    (net (code "45") (name "Net-(LED6-PadA)") (class "Default")
      (node (ref "LED6") (pin "A") (pinfunction "A_A") (pintype "passive"))
      (node (ref "R22") (pin "1") (pinfunction "1_1") (pintype "passive"))
    )
    (net (code "46") (name "Net-(LED7-PadA)") (class "Default")
      (node (ref "LED7") (pin "A") (pinfunction "A_A") (pintype "passive"))
      (node (ref "R23") (pin "1") (pinfunction "1_1") (pintype "passive"))
    )
    (net (code "47") (name "Net-(LED8-PadA)") (class "Default")
      (node (ref "LED8") (pin "A") (pinfunction "A_A") (pintype "passive"))
      (node (ref "R24") (pin "1") (pinfunction "1_1") (pintype "passive"))
    )
    (net (code "48") (name "Net-(LED9-PadA)") (class "Default")
      (node (ref "LED9") (pin "A") (pinfunction "A_A") (pintype "passive"))
      (node (ref "R25") (pin "1") (pinfunction "1_1") (pintype "passive"))
    )
    (net (code "49") (name "Net-(LED10-PadA)") (class "Default")
      (node (ref "LED10") (pin "A") (pinfunction "A_A") (pintype "passive"))
      (node (ref "R26") (pin "1") (pinfunction "1_1") (pintype "passive"))
    )
    (net (code "50") (name "Net-(Q1-D)") (class "Default")
      (node (ref "LED10") (pin "C") (pinfunction "C_C") (pintype "passive"))
      (node (ref "LED3") (pin "C") (pinfunction "C_C") (pintype "passive"))
      (node (ref "LED4") (pin "C") (pinfunction "C_C") (pintype "passive"))
      (node (ref "LED5") (pin "C") (pinfunction "C_C") (pintype "passive"))
      (node (ref "LED6") (pin "C") (pinfunction "C_C") (pintype "passive"))
      (node (ref "LED7") (pin "C") (pinfunction "C_C") (pintype "passive"))
      (node (ref "LED8") (pin "C") (pinfunction "C_C") (pintype "passive"))
      (node (ref "LED9") (pin "C") (pinfunction "C_C") (pintype "passive"))
      (node (ref "Q1") (pin "3") (pinfunction "D_3") (pintype "bidirectional"))
    )
    (net (code "51") (name "Net-(R5-Pad1)") (class "Default")
      (node (ref "R5") (pin "1") (pinfunction "1_1") (pintype "passive"))
      (node (ref "R6") (pin "1") (pinfunction "1_1") (pintype "passive"))
      (node (ref "R7") (pin "1") (pinfunction "1_1") (pintype "passive"))
      (node (ref "R8") (pin "1") (pinfunction "1_1") (pintype "passive"))
      (node (ref "T1") (pin "C") (pinfunction "C_C") (pintype "passive"))
    )
    (net (code "52") (name "Net-(R5-Pad2)") (class "Default")
      (node (ref "R5") (pin "2") (pinfunction "2_2") (pintype "passive"))
      (node (ref "U$10") (pin "P$2") (pinfunction "P$2_P$2") (pintype "bidirectional"))
    )
    (net (code "53") (name "Net-(R6-Pad2)") (class "Default")
      (node (ref "R6") (pin "2") (pinfunction "2_2") (pintype "passive"))
      (node (ref "U$13") (pin "P$2") (pinfunction "P$2_P$2") (pintype "bidirectional"))
    )
    (net (code "54") (name "Net-(R7-Pad2)") (class "Default")
      (node (ref "R7") (pin "2") (pinfunction "2_2") (pintype "passive"))
      (node (ref "U$12") (pin "P$2") (pinfunction "P$2_P$2") (pintype "bidirectional"))
    )
    (net (code "55") (name "Net-(R8-Pad2)") (class "Default")
      (node (ref "R8") (pin "2") (pinfunction "2_2") (pintype "passive"))
      (node (ref "U$8") (pin "P$2") (pinfunction "P$2_P$2") (pintype "bidirectional"))
    )
    (net (code "56") (name "Net-(T2-B)") (class "Default")
      (node (ref "R9") (pin "2") (pinfunction "2_2") (pintype "passive"))
      (node (ref "T1") (pin "E") (pinfunction "E_E") (pintype "passive"))
      (node (ref "T2") (pin "1") (pinfunction "B_1") (pintype "passive"))
      (node (ref "TP2") (pin "TP") (pinfunction "TP_TP") (pintype "input"))
    )
    (net (code "57") (name "Net-(T2-C)") (class "Default")
      (node (ref "R10") (pin "1") (pinfunction "1_1") (pintype "passive"))
      (node (ref "T1") (pin "B") (pinfunction "B_B") (pintype "passive"))
      (node (ref "T2") (pin "3") (pinfunction "C_3") (pintype "passive"))
    )
    (net (code "58") (name "Net-(U$1-OUT1)") (class "Default")
      (node (ref "U$1") (pin "P$6") (pinfunction "OUT1_P$6") (pintype "bidirectional"))
      (node (ref "U$4") (pin "P$2") (pinfunction "M2_P$2") (pintype "bidirectional"))
    )
    (net (code "59") (name "Net-(U$1-OUT2)") (class "Default")
      (node (ref "U$1") (pin "P$4") (pinfunction "OUT2_P$4") (pintype "bidirectional"))
      (node (ref "U$4") (pin "P$1") (pinfunction "M1_P$1") (pintype "bidirectional"))
    )
    (net (code "60") (name "Net-(U$3-OUT1)") (class "Default")
      (node (ref "U$3") (pin "P$6") (pinfunction "OUT1_P$6") (pintype "bidirectional"))
      (node (ref "U$5") (pin "P$2") (pinfunction "M2_P$2") (pintype "bidirectional"))
    )
    (net (code "61") (name "Net-(U$3-OUT2)") (class "Default")
      (node (ref "U$3") (pin "P$4") (pinfunction "OUT2_P$4") (pintype "bidirectional"))
      (node (ref "U$5") (pin "P$1") (pinfunction "M1_P$1") (pintype "bidirectional"))
    )
    (net (code "62") (name "Net-(U2-BST)") (class "Default")
      (node (ref "C12") (pin "1") (pinfunction "1_1") (pintype "passive"))
      (node (ref "U2") (pin "6") (pinfunction "BST_6") (pintype "bidirectional"))
    )
    (net (code "63") (name "Net-(U3A-PH0-OSC_IN)") (class "Default")
      (node (ref "C20") (pin "1") (pinfunction "1_1") (pintype "passive"))
      (node (ref "U3") (pin "5") (pinfunction "PH0-OSC_IN_5") (pintype "bidirectional"))
      (node (ref "Y1") (pin "3") (pinfunction "2_3") (pintype "passive"))
    )
    (net (code "64") (name "Net-(U3A-PH1-OSC_OUT)") (class "Default")
      (node (ref "C21") (pin "1") (pinfunction "1_1") (pintype "passive"))
      (node (ref "U3") (pin "6") (pinfunction "PH1-OSC_OUT_6") (pintype "bidirectional"))
      (node (ref "Y1") (pin "1") (pinfunction "1_1") (pintype "passive"))
    )
    (net (code "65") (name "Net-(U3B-VCAP_1)") (class "Default")
      (node (ref "C22") (pin "2") (pinfunction "2_2") (pintype "passive"))
      (node (ref "U3") (pin "30") (pinfunction "VCAP_1_30") (pintype "power_in"))
    )
    (net (code "66") (name "VCC") (class "Default")
      (node (ref "BATT") (pin "2") (pinfunction "2_2") (pintype "passive"))
      (node (ref "C10") (pin "+") (pinfunction "+_+") (pintype "passive"))
      (node (ref "C11") (pin "+") (pinfunction "+_+") (pintype "passive"))
      (node (ref "C13") (pin "2") (pinfunction "2_2") (pintype "passive"))
      (node (ref "C14") (pin "2") (pinfunction "2_2") (pintype "passive"))
      (node (ref "C4") (pin "1") (pinfunction "1_1") (pintype "passive"))
      (node (ref "C5") (pin "1") (pinfunction "1_1") (pintype "passive"))
      (node (ref "C6") (pin "1") (pinfunction "1_1") (pintype "passive"))
      (node (ref "C7") (pin "1") (pinfunction "1_1") (pintype "passive"))
      (node (ref "D1") (pin "C") (pinfunction "C_C") (pintype "passive"))
      (node (ref "U$1") (pin "P$5") (pinfunction "VM_P$5") (pintype "bidirectional"))
      (node (ref "U$10") (pin "P$1") (pinfunction "P$1_P$1") (pintype "bidirectional"))
      (node (ref "U$12") (pin "P$1") (pinfunction "P$1_P$1") (pintype "bidirectional"))
      (node (ref "U$13") (pin "P$1") (pinfunction "P$1_P$1") (pintype "bidirectional"))
      (node (ref "U$3") (pin "P$5") (pinfunction "VM_P$5") (pintype "bidirectional"))
      (node (ref "U$8") (pin "P$1") (pinfunction "P$1_P$1") (pintype "bidirectional"))
      (node (ref "U2") (pin "2") (pinfunction "EN_2") (pintype "bidirectional"))
      (node (ref "U2") (pin "3") (pinfunction "VIN_3") (pintype "bidirectional"))
    )
    (net (code "67") (name "unconnected-(U$6-INT1-PadP$4)") (class "Default")
      (node (ref "U$6") (pin "P$4") (pinfunction "INT1_P$4") (pintype "bidirectional"))
    )
    (net (code "68") (name "unconnected-(U$6-INT2-PadP$9)") (class "Default")
      (node (ref "U$6") (pin "P$9") (pinfunction "INT2_P$9") (pintype "bidirectional"))
    )
    (net (code "69") (name "unconnected-(U$6-NC1-PadP$10)") (class "Default")
      (node (ref "U$6") (pin "P$10") (pinfunction "NC1_P$10") (pintype "bidirectional"))
    )
    (net (code "70") (name "unconnected-(U$6-NC2-PadP$11)") (class "Default")
      (node (ref "U$6") (pin "P$11") (pinfunction "NC2_P$11") (pintype "bidirectional"))
    )
    (net (code "71") (name "unconnected-(U1-TNOW-Pad6)") (class "Default")
      (node (ref "U1") (pin "6") (pinfunction "TNOW_6") (pintype "bidirectional"))
    )
    (net (code "72") (name "unconnected-(U1-~{CTS}-Pad5)") (class "Default")
      (node (ref "U1") (pin "5") (pinfunction "~{CTS}_5") (pintype "bidirectional"))
    )
    (net (code "73") (name "unconnected-(U1-~{RTS}-Pad4)") (class "Default")
      (node (ref "U1") (pin "4") (pinfunction "~{RTS}_4") (pintype "bidirectional"))
    )
    (net (code "74") (name "unconnected-(U3A-PA8-Pad41)") (class "Default")
      (node (ref "U3") (pin "41") (pinfunction "PA8_41") (pintype "bidirectional"))
    )
    (net (code "75") (name "unconnected-(U3A-PA11-Pad44)") (class "Default")
      (node (ref "U3") (pin "44") (pinfunction "PA11_44") (pintype "bidirectional"))
    )
    (net (code "76") (name "unconnected-(U3A-PA12-Pad45)") (class "Default")
      (node (ref "U3") (pin "45") (pinfunction "PA12_45") (pintype "bidirectional"))
    )
    (net (code "77") (name "unconnected-(U3A-PA13-Pad46)") (class "Default")
      (node (ref "U3") (pin "46") (pinfunction "PA13_46") (pintype "bidirectional"))
    )
    (net (code "78") (name "unconnected-(U3A-PA14-Pad49)") (class "Default")
      (node (ref "U3") (pin "49") (pinfunction "PA14_49") (pintype "bidirectional"))
    )
    (net (code "79") (name "unconnected-(U3A-PA15-Pad50)") (class "Default")
      (node (ref "U3") (pin "50") (pinfunction "PA15_50") (pintype "bidirectional"))
    )
    (net (code "80") (name "unconnected-(U3A-PB3-Pad55)") (class "Default")
      (node (ref "U3") (pin "55") (pinfunction "PB3_55") (pintype "bidirectional"))
    )
    (net (code "81") (name "unconnected-(U3A-PB4-Pad56)") (class "Default")
      (node (ref "U3") (pin "56") (pinfunction "PB4_56") (pintype "bidirectional"))
    )
    (net (code "82") (name "unconnected-(U3A-PB8-Pad61)") (class "Default")
      (node (ref "U3") (pin "61") (pinfunction "PB8_61") (pintype "bidirectional"))
    )
    (net (code "83") (name "unconnected-(U3A-PB9-Pad62)") (class "Default")
      (node (ref "U3") (pin "62") (pinfunction "PB9_62") (pintype "bidirectional"))
    )
    (net (code "84") (name "unconnected-(U3A-PB12-Pad33)") (class "Default")
      (node (ref "U3") (pin "33") (pinfunction "PB12_33") (pintype "bidirectional"))
    )
    (net (code "85") (name "unconnected-(U3A-PB13-Pad34)") (class "Default")
      (node (ref "U3") (pin "34") (pinfunction "PB13_34") (pintype "bidirectional"))
    )
    (net (code "86") (name "unconnected-(U3A-PB14-Pad35)") (class "Default")
      (node (ref "U3") (pin "35") (pinfunction "PB14_35") (pintype "bidirectional"))
    )
    (net (code "87") (name "unconnected-(U3A-PB15-Pad36)") (class "Default")
      (node (ref "U3") (pin "36") (pinfunction "PB15_36") (pintype "bidirectional"))
    )
    (net (code "88") (name "unconnected-(U3A-PC8-Pad39)") (class "Default")
      (node (ref "U3") (pin "39") (pinfunction "PC8_39") (pintype "bidirectional"))
    )
    (net (code "89") (name "unconnected-(U3A-PC9-Pad40)") (class "Default")
      (node (ref "U3") (pin "40") (pinfunction "PC9_40") (pintype "bidirectional"))
    )
    (net (code "90") (name "unconnected-(U3A-PC13-Pad2)") (class "Default")
      (node (ref "U3") (pin "2") (pinfunction "PC13_2") (pintype "bidirectional"))
    )
    (net (code "91") (name "unconnected-(U3A-PC14-OSC32_IN-Pad3)") (class "Default")
      (node (ref "U3") (pin "3") (pinfunction "PC14-OSC32_IN_3") (pintype "bidirectional"))
    )
    (net (code "92") (name "unconnected-(U3A-PC15-OSC32_OUT-Pad4)") (class "Default")
      (node (ref "U3") (pin "4") (pinfunction "PC15-OSC32_OUT_4") (pintype "bidirectional"))
    )
    (net (code "93") (name "unconnected-(U3A-PD2-Pad54)") (class "Default")
      (node (ref "U3") (pin "54") (pinfunction "PD2_54") (pintype "bidirectional"))
    )
  )
)
